# Adafruit_HUSB238_USB-C_PD_Breakout.net
KiCad netlist of a schematic drawn in EAGLE
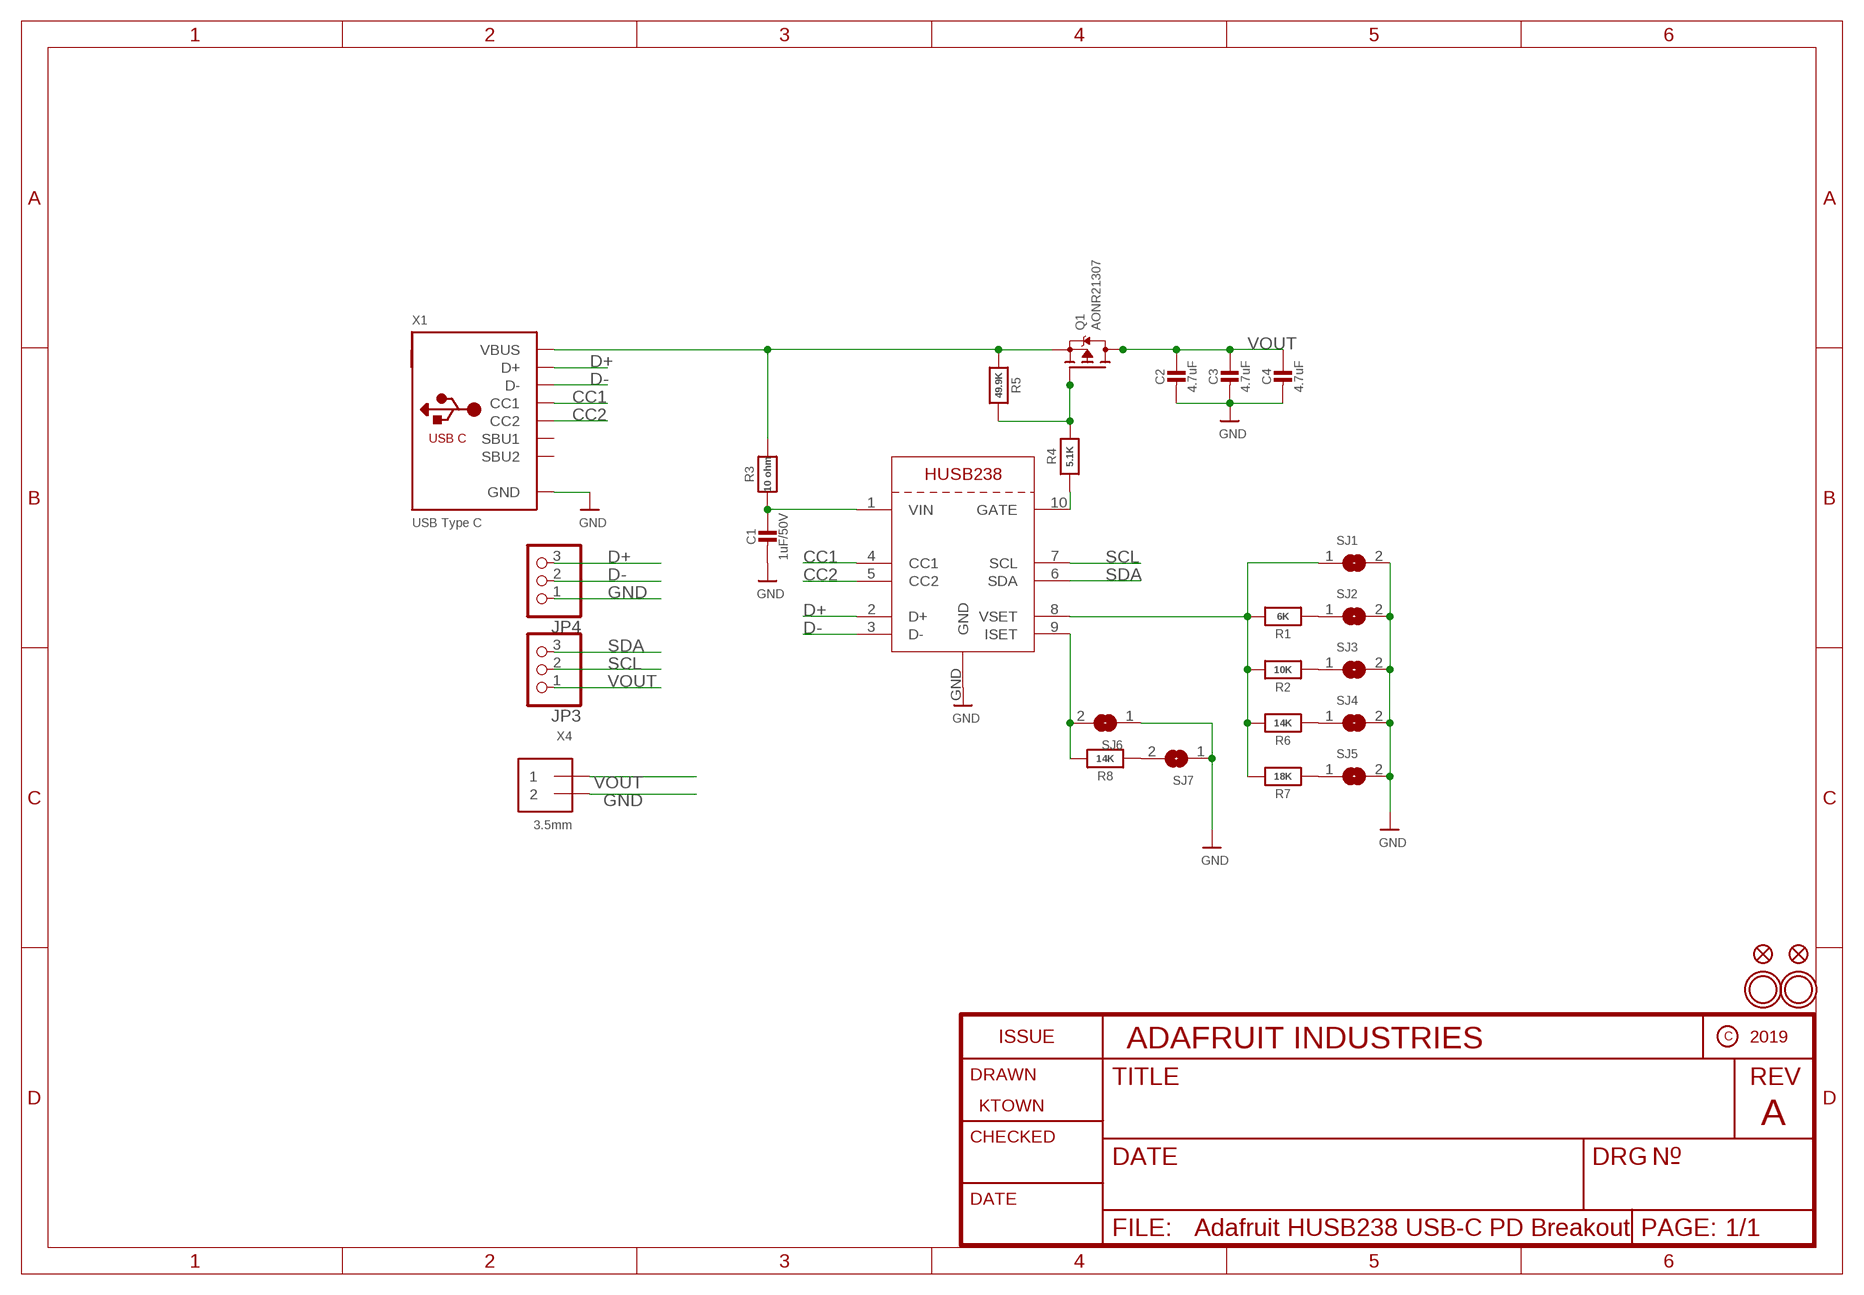
[diagram p0: schematic, sheet 1]

(export (version "E")
  (design (tool "Eeschema 10.0.6"))
  (components
    (comp (ref "C1")
      (value "1uF/50V")
      (footprint "eagle-import:0805-NO")
      (libsource (lib "eagle-import") (part "CAP_CERAMIC0805-NOOUTLINE"))
    )
    (comp (ref "C2")
      (value "4.7uF")
      (footprint "eagle-import:0805-NO")
      (libsource (lib "eagle-import") (part "CAP_CERAMIC0805-NOOUTLINE"))
    )
    (comp (ref "C3")
      (value "4.7uF")
      (footprint "eagle-import:0805-NO")
      (libsource (lib "eagle-import") (part "CAP_CERAMIC0805-NOOUTLINE"))
    )
    (comp (ref "C4")
      (value "4.7uF")
      (footprint "eagle-import:0805-NO")
      (libsource (lib "eagle-import") (part "CAP_CERAMIC0805-NOOUTLINE"))
    )
    (comp (ref "FID1")
      (value "FIDUCIAL_1MM")
      (footprint "eagle-import:FIDUCIAL_1MM")
      (libsource (lib "eagle-import") (part "FIDUCIAL_1MM"))
    )
    (comp (ref "FID2")
      (value "FIDUCIAL_1MM")
      (footprint "eagle-import:FIDUCIAL_1MM")
      (libsource (lib "eagle-import") (part "FIDUCIAL_1MM"))
    )
    (comp (ref "JP3")
      (value "HEADER-1X3ROUND")
      (footprint "eagle-import:1X03_ROUND")
      (libsource (lib "eagle-import") (part "HEADER-1X3ROUND"))
    )
    (comp (ref "JP4")
      (value "HEADER-1X3ROUND")
      (footprint "eagle-import:1X03_ROUND")
      (libsource (lib "eagle-import") (part "HEADER-1X3ROUND"))
    )
    (comp (ref "Q1")
      (value "AONR21307")
      (footprint "eagle-import:POWERDI3333")
      (libsource (lib "eagle-import") (part "MOSFET-P-POWERDI3333"))
    )
    (comp (ref "R1")
      (value "6K")
      (footprint "eagle-import:0603-NO")
      (libsource (lib "eagle-import") (part "RESISTOR_0603_NOOUT"))
    )
    (comp (ref "R2")
      (value "10K")
      (footprint "eagle-import:0603-NO")
      (libsource (lib "eagle-import") (part "RESISTOR_0603_NOOUT"))
    )
    (comp (ref "R3")
      (value "10 ohm")
      (footprint "eagle-import:0603-NO")
      (libsource (lib "eagle-import") (part "RESISTOR_0603_NOOUT"))
    )
    (comp (ref "R4")
      (value "5.1K")
      (footprint "eagle-import:0603-NO")
      (libsource (lib "eagle-import") (part "RESISTOR_0603_NOOUT"))
    )
    (comp (ref "R5")
      (value "49.9K")
      (footprint "eagle-import:0603-NO")
      (libsource (lib "eagle-import") (part "RESISTOR_0603_NOOUT"))
    )
    (comp (ref "R6")
      (value "14K")
      (footprint "eagle-import:0603-NO")
      (libsource (lib "eagle-import") (part "RESISTOR_0603_NOOUT"))
    )
    (comp (ref "R7")
      (value "18K")
      (footprint "eagle-import:0603-NO")
      (libsource (lib "eagle-import") (part "RESISTOR_0603_NOOUT"))
    )
    (comp (ref "R8")
      (value "14K")
      (footprint "eagle-import:0603-NO")
      (libsource (lib "eagle-import") (part "RESISTOR_0603_NOOUT"))
    )
    (comp (ref "SJ1")
      (value "SOLDERJUMPERCLOSED")
      (footprint "eagle-import:SOLDERJUMPER_CLOSEDWIRE")
      (libsource (lib "eagle-import") (part "SOLDERJUMPERCLOSED"))
    )
    (comp (ref "SJ2")
      (value "SOLDERJUMPER")
      (footprint "eagle-import:SOLDERJUMPER_ARROW_NOPASTE")
      (libsource (lib "eagle-import") (part "SOLDERJUMPER"))
    )
    (comp (ref "SJ3")
      (value "SOLDERJUMPER")
      (footprint "eagle-import:SOLDERJUMPER_ARROW_NOPASTE")
      (libsource (lib "eagle-import") (part "SOLDERJUMPER"))
    )
    (comp (ref "SJ4")
      (value "SOLDERJUMPER")
      (footprint "eagle-import:SOLDERJUMPER_ARROW_NOPASTE")
      (libsource (lib "eagle-import") (part "SOLDERJUMPER"))
    )
    (comp (ref "SJ5")
      (value "SOLDERJUMPER")
      (footprint "eagle-import:SOLDERJUMPER_ARROW_NOPASTE")
      (libsource (lib "eagle-import") (part "SOLDERJUMPER"))
    )
    (comp (ref "SJ6")
      (value "SOLDERJUMPERCLOSED")
      (footprint "eagle-import:SOLDERJUMPER_CLOSEDWIRE")
      (libsource (lib "eagle-import") (part "SOLDERJUMPERCLOSED"))
    )
    (comp (ref "SJ7")
      (value "SOLDERJUMPER")
      (footprint "eagle-import:SOLDERJUMPER_ARROW_NOPASTE")
      (libsource (lib "eagle-import") (part "SOLDERJUMPER"))
    )
    (comp (ref "U$1")
      (value "MOUNTINGHOLE2.5")
      (footprint "eagle-import:MOUNTINGHOLE_2.5_PLATED")
      (libsource (lib "eagle-import") (part "MOUNTINGHOLE2.5"))
    )
    (comp (ref "U$2")
      (value "MOUNTINGHOLE2.5")
      (footprint "eagle-import:MOUNTINGHOLE_2.5_PLATED")
      (libsource (lib "eagle-import") (part "MOUNTINGHOLE2.5"))
    )
    (comp (ref "X1")
      (value "USB Type C")
      (footprint "eagle-import:USB_C_CUSB31-CFM2AX-01-X")
      (libsource (lib "eagle-import") (part "USB_C"))
    )
    (comp (ref "X3")
      (value "HUSB238")
      (footprint "eagle-import:DFN10_3X3MM")
      (libsource (lib "eagle-import") (part "HUSB238"))
    )
    (comp (ref "X4")
      (value "3.5mm")
      (footprint "eagle-import:TERMBLOCK_1X2-3.5MM")
      (libsource (lib "eagle-import") (part "TERMBLOCK_1X2_3.5MM"))
    )
  )
  (nets
    (net (code "1") (name "/CC1") (class "Default")
      (node (ref "X1") (pin "A5") (pinfunction "CC1_A5") (pintype "bidirectional"))
      (node (ref "X3") (pin "4") (pinfunction "CC1_4") (pintype "input"))
    )
    (net (code "2") (name "/CC2") (class "Default")
      (node (ref "X1") (pin "B5") (pinfunction "CC2_B5") (pintype "bidirectional"))
      (node (ref "X3") (pin "5") (pinfunction "CC2_5") (pintype "input"))
    )
    (net (code "3") (name "/D+") (class "Default")
      (node (ref "JP4") (pin "3") (pinfunction "3_3") (pintype "passive"))
      (node (ref "X1") (pin "A6") (pinfunction "D+_A6") (pintype "bidirectional"))
      (node (ref "X1") (pin "B6") (pinfunction "D+_B6") (pintype "bidirectional"))
      (node (ref "X3") (pin "2") (pinfunction "D+_2") (pintype "input"))
    )
    (net (code "4") (name "/D-") (class "Default")
      (node (ref "JP4") (pin "2") (pinfunction "2_2") (pintype "passive"))
      (node (ref "X1") (pin "A7") (pinfunction "D-_A7") (pintype "bidirectional"))
      (node (ref "X1") (pin "B7") (pinfunction "D-_B7") (pintype "bidirectional"))
      (node (ref "X3") (pin "3") (pinfunction "D-_3") (pintype "input"))
    )
    (net (code "5") (name "/SCL") (class "Default")
      (node (ref "JP3") (pin "2") (pinfunction "2_2") (pintype "passive"))
      (node (ref "X3") (pin "7") (pinfunction "SCL_7") (pintype "bidirectional"))
    )
    (net (code "6") (name "/SDA") (class "Default")
      (node (ref "JP3") (pin "3") (pinfunction "3_3") (pintype "passive"))
      (node (ref "X3") (pin "6") (pinfunction "SDA_6") (pintype "bidirectional"))
    )
    (net (code "7") (name "/VOUT") (class "Default")
      (node (ref "C2") (pin "1") (pinfunction "1_1") (pintype "passive"))
      (node (ref "C3") (pin "1") (pinfunction "1_1") (pintype "passive"))
      (node (ref "C4") (pin "1") (pinfunction "1_1") (pintype "passive"))
      (node (ref "JP3") (pin "1") (pinfunction "1_1") (pintype "passive"))
      (node (ref "Q1") (pin "5678") (pinfunction "D_5678") (pintype "passive"))
      (node (ref "X4") (pin "1") (pinfunction "1_1") (pintype "passive"))
    )
    (net (code "8") (name "GND") (class "Default")
      (node (ref "C1") (pin "2") (pinfunction "2_2") (pintype "passive"))
      (node (ref "C2") (pin "2") (pinfunction "2_2") (pintype "passive"))
      (node (ref "C3") (pin "2") (pinfunction "2_2") (pintype "passive"))
      (node (ref "C4") (pin "2") (pinfunction "2_2") (pintype "passive"))
      (node (ref "JP4") (pin "1") (pinfunction "1_1") (pintype "passive"))
      (node (ref "SJ1") (pin "2") (pinfunction "2_2") (pintype "passive"))
      (node (ref "SJ2") (pin "2") (pinfunction "2_2") (pintype "passive"))
      (node (ref "SJ3") (pin "2") (pinfunction "2_2") (pintype "passive"))
      (node (ref "SJ4") (pin "2") (pinfunction "2_2") (pintype "passive"))
      (node (ref "SJ5") (pin "2") (pinfunction "2_2") (pintype "passive"))
      (node (ref "SJ6") (pin "1") (pinfunction "1_1") (pintype "passive"))
      (node (ref "SJ7") (pin "1") (pinfunction "1_1") (pintype "passive"))
      (node (ref "X1") (pin "A1B12") (pinfunction "GND_A1B12") (pintype "power_in"))
      (node (ref "X1") (pin "B1A12") (pinfunction "GND_B1A12") (pintype "power_in"))
      (node (ref "X3") (pin "GND") (pinfunction "GND_GND") (pintype "power_in"))
      (node (ref "X4") (pin "2") (pinfunction "2_2") (pintype "passive"))
    )
    (net (code "9") (name "Net-(Q1-G)") (class "Default")
      (node (ref "Q1") (pin "4") (pinfunction "G_4") (pintype "passive"))
      (node (ref "R4") (pin "2") (pinfunction "2_2") (pintype "passive"))
      (node (ref "R5") (pin "2") (pinfunction "2_2") (pintype "passive"))
    )
    (net (code "10") (name "Net-(Q1-S-Pad1)") (class "Default")
      (node (ref "Q1") (pin "1") (pinfunction "S_1") (pintype "passive"))
      (node (ref "Q1") (pin "2") (pinfunction "S_2") (pintype "passive"))
      (node (ref "Q1") (pin "3") (pinfunction "S_3") (pintype "passive"))
      (node (ref "R3") (pin "2") (pinfunction "2_2") (pintype "passive"))
      (node (ref "R5") (pin "1") (pinfunction "1_1") (pintype "passive"))
      (node (ref "X1") (pin "A4B9") (pinfunction "VBUS_A4B9") (pintype "power_in"))
      (node (ref "X1") (pin "B4A9") (pinfunction "VBUS_B4A9") (pintype "power_in"))
    )
    (net (code "11") (name "Net-(R1-Pad1)") (class "Default")
      (node (ref "R1") (pin "1") (pinfunction "1_1") (pintype "passive"))
      (node (ref "SJ2") (pin "1") (pinfunction "1_1") (pintype "passive"))
    )
    (net (code "12") (name "Net-(R2-Pad1)") (class "Default")
      (node (ref "R2") (pin "1") (pinfunction "1_1") (pintype "passive"))
      (node (ref "SJ3") (pin "1") (pinfunction "1_1") (pintype "passive"))
    )
    (net (code "13") (name "Net-(R6-Pad1)") (class "Default")
      (node (ref "R6") (pin "1") (pinfunction "1_1") (pintype "passive"))
      (node (ref "SJ4") (pin "1") (pinfunction "1_1") (pintype "passive"))
    )
    (net (code "14") (name "Net-(R7-Pad1)") (class "Default")
      (node (ref "R7") (pin "1") (pinfunction "1_1") (pintype "passive"))
      (node (ref "SJ5") (pin "1") (pinfunction "1_1") (pintype "passive"))
    )
    (net (code "15") (name "Net-(R8-Pad1)") (class "Default")
      (node (ref "R8") (pin "1") (pinfunction "1_1") (pintype "passive"))
      (node (ref "SJ7") (pin "2") (pinfunction "2_2") (pintype "passive"))
    )
    (net (code "16") (name "Net-(X3-GATE)") (class "Default")
      (node (ref "R4") (pin "1") (pinfunction "1_1") (pintype "passive"))
      (node (ref "X3") (pin "10") (pinfunction "GATE_10") (pintype "output"))
    )
    (net (code "17") (name "Net-(X3-ISET)") (class "Default")
      (node (ref "R8") (pin "2") (pinfunction "2_2") (pintype "passive"))
      (node (ref "SJ6") (pin "2") (pinfunction "2_2") (pintype "passive"))
      (node (ref "X3") (pin "9") (pinfunction "ISET_9") (pintype "passive"))
    )
    (net (code "18") (name "Net-(X3-VIN)") (class "Default")
      (node (ref "C1") (pin "1") (pinfunction "1_1") (pintype "passive"))
      (node (ref "R3") (pin "1") (pinfunction "1_1") (pintype "passive"))
      (node (ref "X3") (pin "1") (pinfunction "VIN_1") (pintype "power_in"))
    )
    (net (code "19") (name "Net-(X3-VSET)") (class "Default")
      (node (ref "R1") (pin "2") (pinfunction "2_2") (pintype "passive"))
      (node (ref "R2") (pin "2") (pinfunction "2_2") (pintype "passive"))
      (node (ref "R6") (pin "2") (pinfunction "2_2") (pintype "passive"))
      (node (ref "R7") (pin "2") (pinfunction "2_2") (pintype "passive"))
      (node (ref "SJ1") (pin "1") (pinfunction "1_1") (pintype "passive"))
      (node (ref "X3") (pin "8") (pinfunction "VSET_8") (pintype "passive"))
    )
    (net (code "20") (name "unconnected-(X1-SBU1-PadA8)") (class "Default")
      (node (ref "X1") (pin "A8") (pinfunction "SBU1_A8") (pintype "bidirectional"))
    )
    (net (code "21") (name "unconnected-(X1-SBU2-PadB8)") (class "Default")
      (node (ref "X1") (pin "B8") (pinfunction "SBU2_B8") (pintype "bidirectional"))
    )
  )
)
